# Main_PCB_Sig_only.net
KiCad netlist of a schematic drawn in EAGLE
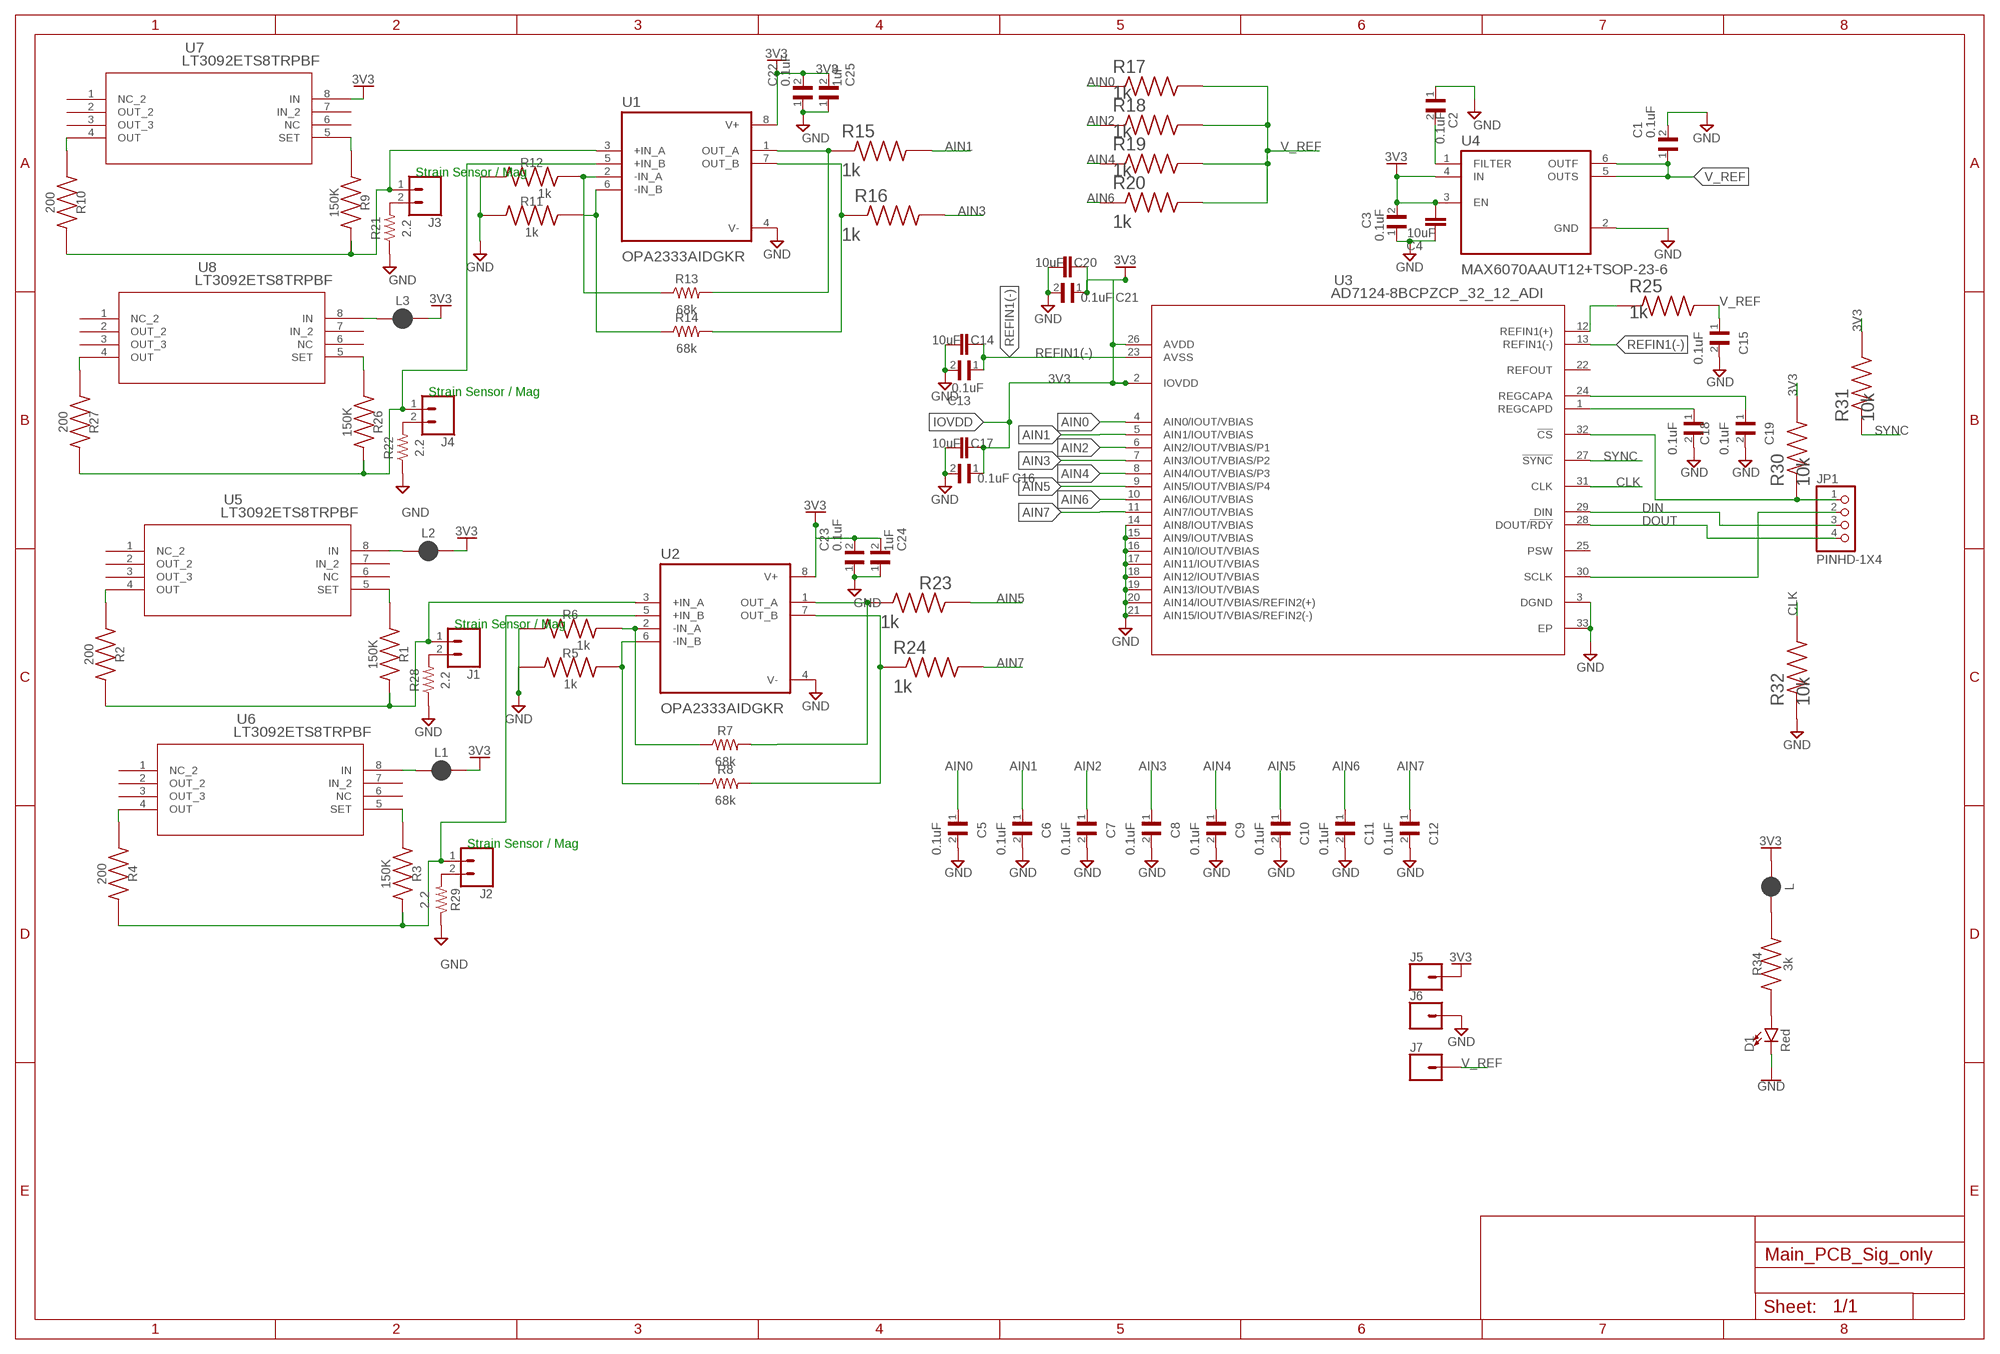
[diagram p0: schematic, sheet 1]

(export (version "E")
  (design (tool "Eeschema 10.0.6"))
  (components
    (comp (ref "C1")
      (value "0.1uF")
      (footprint "eagle-import:CAPC0603X33N")
      (fields (field (name "MF") "AVX") (field (name "MP") "0201ZD104KAT2A"))
      (libsource (lib "eagle-import") (part "0201ZD104KAT2A"))
    )
    (comp (ref "C2")
      (value "0.1uF")
      (footprint "eagle-import:CAPC0603X33N")
      (fields (field (name "MF") "AVX") (field (name "MP") "0201ZD104KAT2A"))
      (libsource (lib "eagle-import") (part "0201ZD104KAT2A"))
    )
    (comp (ref "C3")
      (value "0.1uF")
      (footprint "eagle-import:CAPC0603X33N")
      (fields (field (name "MF") "AVX") (field (name "MP") "0201ZD104KAT2A"))
      (libsource (lib "eagle-import") (part "0201ZD104KAT2A"))
    )
    (comp (ref "C4")
      (value "10uF")
      (footprint "eagle-import:CAPC1005X60")
      (libsource (lib "eagle-import") (part "CCHIP-0402(1005-METRIC)_"))
    )
    (comp (ref "C5")
      (value "0.1uF")
      (footprint "eagle-import:CAPC0603X33N")
      (fields (field (name "MF") "TDK") (field (name "MP") "C0603X7S1A104M030BC"))
      (libsource (lib "eagle-import") (part "C0603X7S1A104M030BC0201"))
    )
    (comp (ref "C6")
      (value "0.1uF")
      (footprint "eagle-import:CAPC0603X33N")
      (fields (field (name "MF") "TDK") (field (name "MP") "C0603X7S1A104M030BC"))
      (libsource (lib "eagle-import") (part "C0603X7S1A104M030BC0201"))
    )
    (comp (ref "C7")
      (value "0.1uF")
      (footprint "eagle-import:CAPC0603X33N")
      (fields (field (name "MF") "TDK") (field (name "MP") "C0603X7S1A104M030BC"))
      (libsource (lib "eagle-import") (part "C0603X7S1A104M030BC0201"))
    )
    (comp (ref "C8")
      (value "0.1uF")
      (footprint "eagle-import:CAPC0603X33N")
      (fields (field (name "MF") "TDK") (field (name "MP") "C0603X7S1A104M030BC"))
      (libsource (lib "eagle-import") (part "C0603X7S1A104M030BC0201"))
    )
    (comp (ref "C9")
      (value "0.1uF")
      (footprint "eagle-import:CAPC0603X33N")
      (fields (field (name "MF") "TDK") (field (name "MP") "C0603X7S1A104M030BC"))
      (libsource (lib "eagle-import") (part "C0603X7S1A104M030BC0201"))
    )
    (comp (ref "C10")
      (value "0.1uF")
      (footprint "eagle-import:CAPC0603X33N")
      (fields (field (name "MF") "TDK") (field (name "MP") "C0603X7S1A104M030BC"))
      (libsource (lib "eagle-import") (part "C0603X7S1A104M030BC0201"))
    )
    (comp (ref "C11")
      (value "0.1uF")
      (footprint "eagle-import:CAPC0603X33N")
      (fields (field (name "MF") "TDK") (field (name "MP") "C0603X7S1A104M030BC"))
      (libsource (lib "eagle-import") (part "C0603X7S1A104M030BC0201"))
    )
    (comp (ref "C12")
      (value "0.1uF")
      (footprint "eagle-import:CAPC0603X33N")
      (fields (field (name "MF") "TDK") (field (name "MP") "C0603X7S1A104M030BC"))
      (libsource (lib "eagle-import") (part "C0603X7S1A104M030BC0201"))
    )
    (comp (ref "C13")
      (value "0.1uF")
      (footprint "eagle-import:CAPC0603X33N")
      (fields (field (name "MF") "AVX") (field (name "MP") "0201ZD104KAT2A"))
      (libsource (lib "eagle-import") (part "0201ZD104KAT2A"))
    )
    (comp (ref "C14")
      (value "10uF")
      (footprint "eagle-import:CAPC1005X60")
      (libsource (lib "eagle-import") (part "CCHIP-0402(1005-METRIC)_"))
    )
    (comp (ref "C15")
      (value "0.1uF")
      (footprint "eagle-import:CAPC0603X33N")
      (fields (field (name "MF") "TDK") (field (name "MP") "C0603X7S1A104M030BC"))
      (libsource (lib "eagle-import") (part "C0603X7S1A104M030BC0201"))
    )
    (comp (ref "C16")
      (value "0.1uF")
      (footprint "eagle-import:CAPC0603X33N")
      (fields (field (name "MF") "AVX") (field (name "MP") "0201ZD104KAT2A"))
      (libsource (lib "eagle-import") (part "0201ZD104KAT2A"))
    )
    (comp (ref "C17")
      (value "10uF")
      (footprint "eagle-import:CAPC1005X60")
      (libsource (lib "eagle-import") (part "CCHIP-0402(1005-METRIC)_"))
    )
    (comp (ref "C18")
      (value "0.1uF")
      (footprint "eagle-import:CAPC0603X33N")
      (fields (field (name "MF") "TDK") (field (name "MP") "C0603X7S1A104M030BC"))
      (libsource (lib "eagle-import") (part "C0603X7S1A104M030BC0201"))
    )
    (comp (ref "C19")
      (value "0.1uF")
      (footprint "eagle-import:CAPC0603X33N")
      (fields (field (name "MF") "TDK") (field (name "MP") "C0603X7S1A104M030BC"))
      (libsource (lib "eagle-import") (part "C0603X7S1A104M030BC0201"))
    )
    (comp (ref "C20")
      (value "10uF")
      (footprint "eagle-import:CAPC1005X60")
      (libsource (lib "eagle-import") (part "CCHIP-0402(1005-METRIC)_"))
    )
    (comp (ref "C21")
      (value "0.1uF")
      (footprint "eagle-import:CAPC0603X33N")
      (fields (field (name "MF") "AVX") (field (name "MP") "0201ZD104KAT2A"))
      (libsource (lib "eagle-import") (part "0201ZD104KAT2A"))
    )
    (comp (ref "C22")
      (value "0.1uF")
      (footprint "eagle-import:CAPC0603X33N")
      (fields (field (name "MF") "AVX") (field (name "MP") "0201ZD104KAT2A"))
      (libsource (lib "eagle-import") (part "0201ZD104KAT2A"))
    )
    (comp (ref "C23")
      (value "0.1uF")
      (footprint "eagle-import:CAPC0603X33N")
      (fields (field (name "MF") "AVX") (field (name "MP") "0201ZD104KAT2A"))
      (libsource (lib "eagle-import") (part "0201ZD104KAT2A"))
    )
    (comp (ref "C24")
      (value "1uF")
      (footprint "eagle-import:CAPC0603X33N")
      (fields (field (name "MF") "AVX") (field (name "MP") "0201ZD104KAT2A"))
      (libsource (lib "eagle-import") (part "0201ZD104KAT2A"))
    )
    (comp (ref "C25")
      (value "1uF")
      (footprint "eagle-import:CAPC0603X33N")
      (fields (field (name "MF") "AVX") (field (name "MP") "0201ZD104KAT2A"))
      (libsource (lib "eagle-import") (part "0201ZD104KAT2A"))
    )
    (comp (ref "D1")
      (value "Red")
      (footprint "eagle-import:LED-0603")
      (libsource (lib "eagle-import") (part "LED-RED0603"))
    )
    (comp (ref "J1")
      (value "CONN_02")
      (footprint "eagle-import:1X02")
      (libsource (lib "eagle-import") (part "CONN_02"))
    )
    (comp (ref "J2")
      (value "CONN_02")
      (footprint "eagle-import:1X02")
      (libsource (lib "eagle-import") (part "CONN_02"))
    )
    (comp (ref "J3")
      (value "CONN_02")
      (footprint "eagle-import:1X02")
      (libsource (lib "eagle-import") (part "CONN_02"))
    )
    (comp (ref "J4")
      (value "CONN_02")
      (footprint "eagle-import:1X02")
      (libsource (lib "eagle-import") (part "CONN_02"))
    )
    (comp (ref "J5")
      (value "CONN_01PTH_LONGPAD")
      (footprint "eagle-import:1X01_LONGPAD")
      (libsource (lib "eagle-import") (part "CONN_01PTH_LONGPAD"))
    )
    (comp (ref "J6")
      (value "CONN_01PTH_LONGPAD")
      (footprint "eagle-import:1X01_LONGPAD")
      (libsource (lib "eagle-import") (part "CONN_01PTH_LONGPAD"))
    )
    (comp (ref "J7")
      (value "CONN_01PTH_LONGPAD")
      (footprint "eagle-import:1X01_LONGPAD")
      (libsource (lib "eagle-import") (part "CONN_01PTH_LONGPAD"))
    )
    (comp (ref "JP1")
      (value "PINHD-1X4")
      (footprint "eagle-import:1X04")
      (fields (field (name "MANUFACTURER") "Generic"))
      (libsource (lib "eagle-import") (part "PINHD-1X4"))
    )
    (comp (ref "L")
      (value "JUMPER-SMT_2_NC_PASTE_NO-SILK")
      (footprint "eagle-import:SMT-JUMPER_2_NC_PASTE_NO-SILK")
      (libsource (lib "eagle-import") (part "JUMPER-SMT_2_NC_PASTE_NO-SILK"))
    )
    (comp (ref "L1")
      (value "JUMPER-SMT_2_NC_PASTE_NO-SILK")
      (footprint "eagle-import:SMT-JUMPER_2_NC_PASTE_NO-SILK")
      (libsource (lib "eagle-import") (part "JUMPER-SMT_2_NC_PASTE_NO-SILK"))
    )
    (comp (ref "L2")
      (value "JUMPER-SMT_2_NC_PASTE_NO-SILK")
      (footprint "eagle-import:SMT-JUMPER_2_NC_PASTE_NO-SILK")
      (libsource (lib "eagle-import") (part "JUMPER-SMT_2_NC_PASTE_NO-SILK"))
    )
    (comp (ref "L3")
      (value "JUMPER-SMT_2_NC_PASTE_NO-SILK")
      (footprint "eagle-import:SMT-JUMPER_2_NC_PASTE_NO-SILK")
      (libsource (lib "eagle-import") (part "JUMPER-SMT_2_NC_PASTE_NO-SILK"))
    )
    (comp (ref "R1")
      (value "150K")
      (footprint "eagle-import:RESC0603X26N")
      (fields (field (name "MF") "Yageo") (field (name "MP") "AC0201FR-0710KL"))
      (libsource (lib "eagle-import") (part "AC0201FR-0710KL"))
    )
    (comp (ref "R2")
      (value "200")
      (footprint "eagle-import:RESC0603X26N")
      (fields (field (name "MF") "Yageo") (field (name "MP") "AC0201FR-0710KL"))
      (libsource (lib "eagle-import") (part "AC0201FR-0710KL"))
    )
    (comp (ref "R3")
      (value "150K")
      (footprint "eagle-import:RESC0603X26N")
      (fields (field (name "MF") "Yageo") (field (name "MP") "AC0201FR-0710KL"))
      (libsource (lib "eagle-import") (part "AC0201FR-0710KL"))
    )
    (comp (ref "R4")
      (value "200")
      (footprint "eagle-import:RESC0603X26N")
      (fields (field (name "MF") "Yageo") (field (name "MP") "AC0201FR-0710KL"))
      (libsource (lib "eagle-import") (part "AC0201FR-0710KL"))
    )
    (comp (ref "R5")
      (value "1k")
      (footprint "eagle-import:RESC0603X26N")
      (fields (field (name "MF") "Yageo") (field (name "MP") "AC0201FR-0710KL"))
      (libsource (lib "eagle-import") (part "AC0201FR-0710KL"))
    )
    (comp (ref "R6")
      (value "1k")
      (footprint "eagle-import:RESC0603X26N")
      (fields (field (name "MF") "Yageo") (field (name "MP") "AC0201FR-0710KL"))
      (libsource (lib "eagle-import") (part "AC0201FR-0710KL"))
    )
    (comp (ref "R7")
      (value "68k")
      (footprint "eagle-import:RESC1608X60")
      (libsource (lib "eagle-import") (part "R-USCHIP-0603(1608-METRIC)_"))
    )
    (comp (ref "R8")
      (value "68k")
      (footprint "eagle-import:RESC1608X60")
      (libsource (lib "eagle-import") (part "R-USCHIP-0603(1608-METRIC)_"))
    )
    (comp (ref "R9")
      (value "150K")
      (footprint "eagle-import:RESC0603X26N")
      (fields (field (name "MF") "Yageo") (field (name "MP") "AC0201FR-0710KL"))
      (libsource (lib "eagle-import") (part "AC0201FR-0710KL"))
    )
    (comp (ref "R10")
      (value "200")
      (footprint "eagle-import:RESC0603X26N")
      (fields (field (name "MF") "Yageo") (field (name "MP") "AC0201FR-0710KL"))
      (libsource (lib "eagle-import") (part "AC0201FR-0710KL"))
    )
    (comp (ref "R11")
      (value "1k")
      (footprint "eagle-import:RESC0603X26N")
      (fields (field (name "MF") "Yageo") (field (name "MP") "AC0201FR-0710KL"))
      (libsource (lib "eagle-import") (part "AC0201FR-0710KL"))
    )
    (comp (ref "R12")
      (value "1k")
      (footprint "eagle-import:RESC0603X26N")
      (fields (field (name "MF") "Yageo") (field (name "MP") "AC0201FR-0710KL"))
      (libsource (lib "eagle-import") (part "AC0201FR-0710KL"))
    )
    (comp (ref "R13")
      (value "68k")
      (footprint "eagle-import:RESC1608X60")
      (libsource (lib "eagle-import") (part "R-USCHIP-0603(1608-METRIC)_"))
    )
    (comp (ref "R14")
      (value "68k")
      (footprint "eagle-import:RESC1608X60")
      (libsource (lib "eagle-import") (part "R-USCHIP-0603(1608-METRIC)_"))
    )
    (comp (ref "R15")
      (value "1k")
      (footprint "eagle-import:RESC0603X26N")
      (fields (field (name "MF") "Yageo") (field (name "MP") "AC0201FR-0710KL"))
      (libsource (lib "eagle-import") (part "AC0201FR-0710KL"))
    )
    (comp (ref "R16")
      (value "1k")
      (footprint "eagle-import:RESC0603X26N")
      (fields (field (name "MF") "Yageo") (field (name "MP") "AC0201FR-0710KL"))
      (libsource (lib "eagle-import") (part "AC0201FR-0710KL"))
    )
    (comp (ref "R17")
      (value "1k")
      (footprint "eagle-import:RESC0603X26N")
      (fields (field (name "MF") "Yageo") (field (name "MP") "AC0201FR-0710KL"))
      (libsource (lib "eagle-import") (part "AC0201FR-0710KL"))
    )
    (comp (ref "R18")
      (value "1k")
      (footprint "eagle-import:RESC0603X26N")
      (fields (field (name "MF") "Yageo") (field (name "MP") "AC0201FR-0710KL"))
      (libsource (lib "eagle-import") (part "AC0201FR-0710KL"))
    )
    (comp (ref "R19")
      (value "1k")
      (footprint "eagle-import:RESC0603X26N")
      (fields (field (name "MF") "Yageo") (field (name "MP") "AC0201FR-0710KL"))
      (libsource (lib "eagle-import") (part "AC0201FR-0710KL"))
    )
    (comp (ref "R20")
      (value "1k")
      (footprint "eagle-import:RESC0603X26N")
      (fields (field (name "MF") "Yageo") (field (name "MP") "AC0201FR-0710KL"))
      (libsource (lib "eagle-import") (part "AC0201FR-0710KL"))
    )
    (comp (ref "R21")
      (value "2.2")
      (footprint "eagle-import:RESC1608X60")
      (libsource (lib "eagle-import") (part "R-USCHIP-0603(1608-METRIC)_"))
    )
    (comp (ref "R22")
      (value "2.2")
      (footprint "eagle-import:RESC1608X60")
      (libsource (lib "eagle-import") (part "R-USCHIP-0603(1608-METRIC)_"))
    )
    (comp (ref "R23")
      (value "1k")
      (footprint "eagle-import:RESC0603X26N")
      (fields (field (name "MF") "Yageo") (field (name "MP") "AC0201FR-0710KL"))
      (libsource (lib "eagle-import") (part "AC0201FR-0710KL"))
    )
    (comp (ref "R24")
      (value "1k")
      (footprint "eagle-import:RESC0603X26N")
      (fields (field (name "MF") "Yageo") (field (name "MP") "AC0201FR-0710KL"))
      (libsource (lib "eagle-import") (part "AC0201FR-0710KL"))
    )
    (comp (ref "R25")
      (value "1k")
      (footprint "eagle-import:RESC0603X26N")
      (fields (field (name "MF") "Yageo") (field (name "MP") "AC0201FR-0710KL"))
      (libsource (lib "eagle-import") (part "AC0201FR-0710KL"))
    )
    (comp (ref "R26")
      (value "150K")
      (footprint "eagle-import:RESC0603X26N")
      (fields (field (name "MF") "Yageo") (field (name "MP") "AC0201FR-0710KL"))
      (libsource (lib "eagle-import") (part "AC0201FR-0710KL"))
    )
    (comp (ref "R27")
      (value "200")
      (footprint "eagle-import:RESC0603X26N")
      (fields (field (name "MF") "Yageo") (field (name "MP") "AC0201FR-0710KL"))
      (libsource (lib "eagle-import") (part "AC0201FR-0710KL"))
    )
    (comp (ref "R28")
      (value "2.2")
      (footprint "eagle-import:RESC1608X60")
      (libsource (lib "eagle-import") (part "R-USCHIP-0603(1608-METRIC)_"))
    )
    (comp (ref "R29")
      (value "2.2")
      (footprint "eagle-import:RESC1608X60")
      (libsource (lib "eagle-import") (part "R-USCHIP-0603(1608-METRIC)_"))
    )
    (comp (ref "R30")
      (value "10k")
      (footprint "eagle-import:RESC0603X26N")
      (fields (field (name "MF") "Yageo") (field (name "MP") "AC0201FR-0710KL"))
      (libsource (lib "eagle-import") (part "AC0201FR-0710KL"))
    )
    (comp (ref "R31")
      (value "10k")
      (footprint "eagle-import:RESC0603X26N")
      (fields (field (name "MF") "Yageo") (field (name "MP") "AC0201FR-0710KL"))
      (libsource (lib "eagle-import") (part "AC0201FR-0710KL"))
    )
    (comp (ref "R32")
      (value "10k")
      (footprint "eagle-import:RESC0603X26N")
      (fields (field (name "MF") "Yageo") (field (name "MP") "AC0201FR-0710KL"))
      (libsource (lib "eagle-import") (part "AC0201FR-0710KL"))
    )
    (comp (ref "R34")
      (value "3k")
      (footprint "eagle-import:RESC0603X26N")
      (fields (field (name "MF") "Yageo") (field (name "MP") "AC0201FR-0710KL"))
      (libsource (lib "eagle-import") (part "AC0201FR-0710KL"))
    )
    (comp (ref "U1")
      (value "OPA2333AIDGKR")
      (footprint "eagle-import:SOP65P490X110-8N")
      (fields (field (name "MF") "Texas Instruments"))
      (libsource (lib "eagle-import") (part "OPA2333AIDGKR"))
    )
    (comp (ref "U2")
      (value "OPA2333AIDGKR")
      (footprint "eagle-import:SOP65P490X110-8N")
      (fields (field (name "MF") "Texas Instruments"))
      (libsource (lib "eagle-import") (part "OPA2333AIDGKR"))
    )
    (comp (ref "U3")
      (value "AD7124-8BCPZCP_32_12_ADI")
      (footprint "eagle-import:CP_32_12_ADI")
      (fields
        (field (name "MANUFACTURER_PART_NUMBER") "AD7124-8BCPZ")
        (field (name "COPYRIGHT") "Copyright (C) 2025 Ultra Librarian. All rights reserved.")
      )
      (libsource (lib "eagle-import") (part "AD7124-8BCPZCP_32_12_ADI"))
    )
    (comp (ref "U4")
      (value "MAX6070AAUT12+TSOP-23-6")
      (footprint "eagle-import:SOT95P280X145-6N")
      (fields (field (name "MF") "Maxim Integrated Products") (field (name "MP") "MAX6070AAUT12+T"))
      (libsource (lib "eagle-import") (part "MAX6070AAUT12+TSOP-23-6"))
    )
    (comp (ref "U5")
      (value "LT3092ETS8TRPBF")
      (footprint "eagle-import:TSOT-23_TS8")
      (fields (field (name "MF") "Analog Devices") (field (name "MP") "LT3092ETS8#TRPBF"))
      (libsource (lib "eagle-import") (part "LT3092ETS8TRPBF"))
    )
    (comp (ref "U6")
      (value "LT3092ETS8TRPBF")
      (footprint "eagle-import:TSOT-23_TS8")
      (fields (field (name "MF") "Analog Devices") (field (name "MP") "LT3092ETS8#TRPBF"))
      (libsource (lib "eagle-import") (part "LT3092ETS8TRPBF"))
    )
    (comp (ref "U7")
      (value "LT3092ETS8TRPBF")
      (footprint "eagle-import:TSOT-23_TS8")
      (fields (field (name "MF") "Analog Devices") (field (name "MP") "LT3092ETS8#TRPBF"))
      (libsource (lib "eagle-import") (part "LT3092ETS8TRPBF"))
    )
    (comp (ref "U8")
      (value "LT3092ETS8TRPBF")
      (footprint "eagle-import:TSOT-23_TS8")
      (fields (field (name "MF") "Analog Devices") (field (name "MP") "LT3092ETS8#TRPBF"))
      (libsource (lib "eagle-import") (part "LT3092ETS8TRPBF"))
    )
  )
  (nets
    (net (code "1") (name "/CLK") (class "Default")
      (node (ref "R32") (pin "2") (pinfunction "2_2") (pintype "passive"))
      (node (ref "U3") (pin "31") (pinfunction "CLK_31") (pintype "passive"))
    )
    (net (code "2") (name "/DIN") (class "Default")
      (node (ref "JP1") (pin "3") (pinfunction "3_3") (pintype "passive"))
      (node (ref "U3") (pin "29") (pinfunction "DIN_29") (pintype "passive"))
    )
    (net (code "3") (name "/DOUT") (class "Default")
      (node (ref "JP1") (pin "4") (pinfunction "4_4") (pintype "passive"))
      (node (ref "U3") (pin "28") (pinfunction "DOUT/~{RDY}_28") (pintype "passive"))
    )
    (net (code "4") (name "/SYNC") (class "Default")
      (node (ref "R31") (pin "1") (pinfunction "1_1") (pintype "passive"))
      (node (ref "U3") (pin "27") (pinfunction "~{SYNC}_27") (pintype "passive"))
    )
    (net (code "5") (name "AIN0") (class "Default")
      (node (ref "C5") (pin "1") (pinfunction "1_1") (pintype "passive"))
      (node (ref "R17") (pin "1") (pinfunction "1_1") (pintype "passive"))
      (node (ref "U3") (pin "4") (pinfunction "AIN0/IOUT/VBIAS_4") (pintype "passive"))
    )
    (net (code "6") (name "AIN1") (class "Default")
      (node (ref "C6") (pin "1") (pinfunction "1_1") (pintype "passive"))
      (node (ref "R15") (pin "2") (pinfunction "2_2") (pintype "passive"))
      (node (ref "U3") (pin "5") (pinfunction "AIN1/IOUT/VBIAS_5") (pintype "passive"))
    )
    (net (code "7") (name "AIN2") (class "Default")
      (node (ref "C7") (pin "1") (pinfunction "1_1") (pintype "passive"))
      (node (ref "R18") (pin "1") (pinfunction "1_1") (pintype "passive"))
      (node (ref "U3") (pin "6") (pinfunction "AIN2/IOUT/VBIAS/P1_6") (pintype "passive"))
    )
    (net (code "8") (name "AIN3") (class "Default")
      (node (ref "C8") (pin "1") (pinfunction "1_1") (pintype "passive"))
      (node (ref "R16") (pin "2") (pinfunction "2_2") (pintype "passive"))
      (node (ref "U3") (pin "7") (pinfunction "AIN3/IOUT/VBIAS/P2_7") (pintype "passive"))
    )
    (net (code "9") (name "AIN4") (class "Default")
      (node (ref "C9") (pin "1") (pinfunction "1_1") (pintype "passive"))
      (node (ref "R19") (pin "1") (pinfunction "1_1") (pintype "passive"))
      (node (ref "U3") (pin "8") (pinfunction "AIN4/IOUT/VBIAS/P3_8") (pintype "passive"))
    )
    (net (code "10") (name "AIN5") (class "Default")
      (node (ref "C10") (pin "1") (pinfunction "1_1") (pintype "passive"))
      (node (ref "R23") (pin "2") (pinfunction "2_2") (pintype "passive"))
      (node (ref "U3") (pin "9") (pinfunction "AIN5/IOUT/VBIAS/P4_9") (pintype "passive"))
    )
    (net (code "11") (name "AIN6") (class "Default")
      (node (ref "C11") (pin "1") (pinfunction "1_1") (pintype "passive"))
      (node (ref "R20") (pin "1") (pinfunction "1_1") (pintype "passive"))
      (node (ref "U3") (pin "10") (pinfunction "AIN6/IOUT/VBIAS_10") (pintype "passive"))
    )
    (net (code "12") (name "AIN7") (class "Default")
      (node (ref "C12") (pin "1") (pinfunction "1_1") (pintype "passive"))
      (node (ref "R24") (pin "2") (pinfunction "2_2") (pintype "passive"))
      (node (ref "U3") (pin "11") (pinfunction "AIN7/IOUT/VBIAS_11") (pintype "passive"))
    )
    (net (code "13") (name "GND") (class "Default")
      (node (ref "C1") (pin "2") (pinfunction "2_2") (pintype "passive"))
      (node (ref "C10") (pin "2") (pinfunction "2_2") (pintype "passive"))
      (node (ref "C11") (pin "2") (pinfunction "2_2") (pintype "passive"))
      (node (ref "C12") (pin "2") (pinfunction "2_2") (pintype "passive"))
      (node (ref "C13") (pin "2") (pinfunction "2_2") (pintype "passive"))
      (node (ref "C14") (pin "2") (pinfunction "2_2") (pintype "passive"))
      (node (ref "C15") (pin "2") (pinfunction "2_2") (pintype "passive"))
      (node (ref "C16") (pin "2") (pinfunction "2_2") (pintype "passive"))
      (node (ref "C17") (pin "2") (pinfunction "2_2") (pintype "passive"))
      (node (ref "C18") (pin "2") (pinfunction "2_2") (pintype "passive"))
      (node (ref "C19") (pin "2") (pinfunction "2_2") (pintype "passive"))
      (node (ref "C2") (pin "1") (pinfunction "1_1") (pintype "passive"))
      (node (ref "C20") (pin "2") (pinfunction "2_2") (pintype "passive"))
      (node (ref "C21") (pin "2") (pinfunction "2_2") (pintype "passive"))
      (node (ref "C22") (pin "1") (pinfunction "1_1") (pintype "passive"))
      (node (ref "C23") (pin "1") (pinfunction "1_1") (pintype "passive"))
      (node (ref "C24") (pin "1") (pinfunction "1_1") (pintype "passive"))
      (node (ref "C25") (pin "1") (pinfunction "1_1") (pintype "passive"))
      (node (ref "C3") (pin "1") (pinfunction "1_1") (pintype "passive"))
      (node (ref "C4") (pin "1") (pinfunction "1_1") (pintype "passive"))
      (node (ref "C5") (pin "2") (pinfunction "2_2") (pintype "passive"))
      (node (ref "C6") (pin "2") (pinfunction "2_2") (pintype "passive"))
      (node (ref "C7") (pin "2") (pinfunction "2_2") (pintype "passive"))
      (node (ref "C8") (pin "2") (pinfunction "2_2") (pintype "passive"))
      (node (ref "C9") (pin "2") (pinfunction "2_2") (pintype "passive"))
      (node (ref "D1") (pin "C") (pinfunction "C_C") (pintype "passive"))
      (node (ref "J6") (pin "1") (pinfunction "1_1") (pintype "passive"))
      (node (ref "R11") (pin "1") (pinfunction "1_1") (pintype "passive"))
      (node (ref "R12") (pin "1") (pinfunction "1_1") (pintype "passive"))
      (node (ref "R21") (pin "1") (pinfunction "1_1") (pintype "passive"))
      (node (ref "R22") (pin "1") (pinfunction "1_1") (pintype "passive"))
      (node (ref "R28") (pin "1") (pinfunction "1_1") (pintype "passive"))
      (node (ref "R29") (pin "1") (pinfunction "1_1") (pintype "passive"))
      (node (ref "R32") (pin "1") (pinfunction "1_1") (pintype "passive"))
      (node (ref "R5") (pin "1") (pinfunction "1_1") (pintype "passive"))
      (node (ref "R6") (pin "1") (pinfunction "1_1") (pintype "passive"))
      (node (ref "U1") (pin "4") (pinfunction "V-_4") (pintype "power_in"))
      (node (ref "U2") (pin "4") (pinfunction "V-_4") (pintype "power_in"))
      (node (ref "U3") (pin "14") (pinfunction "AIN8/IOUT/VBIAS_14") (pintype "passive"))
      (node (ref "U3") (pin "15") (pinfunction "AIN9/IOUT/VBIAS_15") (pintype "passive"))
      (node (ref "U3") (pin "16") (pinfunction "AIN10/IOUT/VBIAS_16") (pintype "passive"))
      (node (ref "U3") (pin "17") (pinfunction "AIN11/IOUT/VBIAS_17") (pintype "passive"))
      (node (ref "U3") (pin "18") (pinfunction "AIN12/IOUT/VBIAS_18") (pintype "passive"))
      (node (ref "U3") (pin "19") (pinfunction "AIN13/IOUT/VBIAS_19") (pintype "passive"))
      (node (ref "U3") (pin "20") (pinfunction "AIN14/IOUT/VBIAS/REFIN2(+)_20") (pintype "passive"))
      (node (ref "U3") (pin "21") (pinfunction "AIN15/IOUT/VBIAS/REFIN2(-)_21") (pintype "passive"))
      (node (ref "U3") (pin "3") (pinfunction "DGND_3") (pintype "passive"))
      (node (ref "U3") (pin "33") (pinfunction "EP_33") (pintype "passive"))
      (node (ref "U4") (pin "2") (pinfunction "GND_2") (pintype "power_in"))
    )
    (net (code "14") (name "IOVDD") (class "Default")
      (node (ref "C16") (pin "1") (pinfunction "1_1") (pintype "passive"))
      (node (ref "C17") (pin "1") (pinfunction "1_1") (pintype "passive"))
      (node (ref "C20") (pin "1") (pinfunction "1_1") (pintype "passive"))
      (node (ref "C21") (pin "1") (pinfunction "1_1") (pintype "passive"))
      (node (ref "C22") (pin "2") (pinfunction "2_2") (pintype "passive"))
      (node (ref "C23") (pin "2") (pinfunction "2_2") (pintype "passive"))
      (node (ref "C24") (pin "2") (pinfunction "2_2") (pintype "passive"))
      (node (ref "C25") (pin "2") (pinfunction "2_2") (pintype "passive"))
      (node (ref "C3") (pin "2") (pinfunction "2_2") (pintype "passive"))
      (node (ref "C4") (pin "2") (pinfunction "2_2") (pintype "passive"))
      (node (ref "J5") (pin "1") (pinfunction "1_1") (pintype "passive"))
      (node (ref "L") (pin "1") (pinfunction "1_1") (pintype "passive"))
      (node (ref "L1") (pin "2") (pinfunction "2_2") (pintype "passive"))
      (node (ref "L2") (pin "2") (pinfunction "2_2") (pintype "passive"))
      (node (ref "L3") (pin "2") (pinfunction "2_2") (pintype "passive"))
      (node (ref "R30") (pin "2") (pinfunction "2_2") (pintype "passive"))
      (node (ref "R31") (pin "2") (pinfunction "2_2") (pintype "passive"))
      (node (ref "U1") (pin "8") (pinfunction "V+_8") (pintype "power_in"))
      (node (ref "U2") (pin "8") (pinfunction "V+_8") (pintype "power_in"))
      (node (ref "U3") (pin "2") (pinfunction "IOVDD_2") (pintype "passive"))
      (node (ref "U3") (pin "26") (pinfunction "AVDD_26") (pintype "passive"))
      (node (ref "U4") (pin "3") (pinfunction "EN_3") (pintype "bidirectional"))
      (node (ref "U4") (pin "4") (pinfunction "IN_4") (pintype "input"))
      (node (ref "U7") (pin "8") (pinfunction "IN_8") (pintype "input"))
    )
    (net (code "15") (name "Net-(D1-PadA)") (class "Default")
      (node (ref "D1") (pin "A") (pinfunction "A_A") (pintype "passive"))
      (node (ref "R34") (pin "1") (pinfunction "1_1") (pintype "passive"))
    )
    (net (code "16") (name "Net-(J1-Pad2)") (class "Default")
      (node (ref "J1") (pin "2") (pinfunction "2_2") (pintype "passive"))
      (node (ref "R28") (pin "2") (pinfunction "2_2") (pintype "passive"))
    )
    (net (code "17") (name "Net-(J2-Pad2)") (class "Default")
      (node (ref "J2") (pin "2") (pinfunction "2_2") (pintype "passive"))
      (node (ref "R29") (pin "2") (pinfunction "2_2") (pintype "passive"))
    )
    (net (code "18") (name "Net-(J3-Pad2)") (class "Default")
      (node (ref "J3") (pin "2") (pinfunction "2_2") (pintype "passive"))
      (node (ref "R21") (pin "2") (pinfunction "2_2") (pintype "passive"))
    )
    (net (code "19") (name "Net-(J4-Pad2)") (class "Default")
      (node (ref "J4") (pin "2") (pinfunction "2_2") (pintype "passive"))
      (node (ref "R22") (pin "2") (pinfunction "2_2") (pintype "passive"))
    )
    (net (code "20") (name "Net-(L-Pad2)") (class "Default")
      (node (ref "L") (pin "2") (pinfunction "2_2") (pintype "passive"))
      (node (ref "R34") (pin "2") (pinfunction "2_2") (pintype "passive"))
    )
    (net (code "21") (name "Net-(U1-+IN_A)") (class "Default")
      (node (ref "J3") (pin "1") (pinfunction "1_1") (pintype "passive"))
      (node (ref "R10") (pin "2") (pinfunction "2_2") (pintype "passive"))
      (node (ref "R9") (pin "2") (pinfunction "2_2") (pintype "passive"))
      (node (ref "U1") (pin "3") (pinfunction "+IN_A_3") (pintype "input"))
    )
    (net (code "22") (name "Net-(U1-+IN_B)") (class "Default")
      (node (ref "J4") (pin "1") (pinfunction "1_1") (pintype "passive"))
      (node (ref "R26") (pin "2") (pinfunction "2_2") (pintype "passive"))
      (node (ref "R27") (pin "2") (pinfunction "2_2") (pintype "passive"))
      (node (ref "U1") (pin "5") (pinfunction "+IN_B_5") (pintype "input"))
    )
    (net (code "23") (name "Net-(U1--IN_A)") (class "Default")
      (node (ref "R12") (pin "2") (pinfunction "2_2") (pintype "passive"))
      (node (ref "R13") (pin "1") (pinfunction "1_1") (pintype "passive"))
      (node (ref "U1") (pin "2") (pinfunction "-IN_A_2") (pintype "input"))
    )
    (net (code "24") (name "Net-(U1--IN_B)") (class "Default")
      (node (ref "R11") (pin "2") (pinfunction "2_2") (pintype "passive"))
      (node (ref "R14") (pin "1") (pinfunction "1_1") (pintype "passive"))
      (node (ref "U1") (pin "6") (pinfunction "-IN_B_6") (pintype "input"))
    )
    (net (code "25") (name "Net-(U1-OUT_A)") (class "Default")
      (node (ref "R13") (pin "2") (pinfunction "2_2") (pintype "passive"))
      (node (ref "R15") (pin "1") (pinfunction "1_1") (pintype "passive"))
      (node (ref "U1") (pin "1") (pinfunction "OUT_A_1") (pintype "output"))
    )
    (net (code "26") (name "Net-(U1-OUT_B)") (class "Default")
      (node (ref "R14") (pin "2") (pinfunction "2_2") (pintype "passive"))
      (node (ref "R16") (pin "1") (pinfunction "1_1") (pintype "passive"))
      (node (ref "U1") (pin "7") (pinfunction "OUT_B_7") (pintype "output"))
    )
    (net (code "27") (name "Net-(U2-+IN_A)") (class "Default")
      (node (ref "J1") (pin "1") (pinfunction "1_1") (pintype "passive"))
      (node (ref "R1") (pin "2") (pinfunction "2_2") (pintype "passive"))
      (node (ref "R2") (pin "2") (pinfunction "2_2") (pintype "passive"))
      (node (ref "U2") (pin "3") (pinfunction "+IN_A_3") (pintype "input"))
    )
    (net (code "28") (name "Net-(U2-+IN_B)") (class "Default")
      (node (ref "J2") (pin "1") (pinfunction "1_1") (pintype "passive"))
      (node (ref "R3") (pin "2") (pinfunction "2_2") (pintype "passive"))
      (node (ref "R4") (pin "2") (pinfunction "2_2") (pintype "passive"))
      (node (ref "U2") (pin "5") (pinfunction "+IN_B_5") (pintype "input"))
    )
    (net (code "29") (name "Net-(U2--IN_A)") (class "Default")
      (node (ref "R6") (pin "2") (pinfunction "2_2") (pintype "passive"))
      (node (ref "R7") (pin "1") (pinfunction "1_1") (pintype "passive"))
      (node (ref "U2") (pin "2") (pinfunction "-IN_A_2") (pintype "input"))
    )
    (net (code "30") (name "Net-(U2--IN_B)") (class "Default")
      (node (ref "R5") (pin "2") (pinfunction "2_2") (pintype "passive"))
      (node (ref "R8") (pin "1") (pinfunction "1_1") (pintype "passive"))
      (node (ref "U2") (pin "6") (pinfunction "-IN_B_6") (pintype "input"))
    )
    (net (code "31") (name "Net-(U2-OUT_A)") (class "Default")
      (node (ref "R23") (pin "1") (pinfunction "1_1") (pintype "passive"))
      (node (ref "R7") (pin "2") (pinfunction "2_2") (pintype "passive"))
      (node (ref "U2") (pin "1") (pinfunction "OUT_A_1") (pintype "output"))
    )
    (net (code "32") (name "Net-(U2-OUT_B)") (class "Default")
      (node (ref "R24") (pin "1") (pinfunction "1_1") (pintype "passive"))
      (node (ref "R8") (pin "2") (pinfunction "2_2") (pintype "passive"))
      (node (ref "U2") (pin "7") (pinfunction "OUT_B_7") (pintype "output"))
    )
    (net (code "33") (name "Net-(U3-REFIN1(+))") (class "Default")
      (node (ref "R25") (pin "1") (pinfunction "1_1") (pintype "passive"))
      (node (ref "U3") (pin "12") (pinfunction "REFIN1(+)_12") (pintype "passive"))
    )
    (net (code "34") (name "Net-(U3-REGCAPA)") (class "Default")
      (node (ref "C19") (pin "1") (pinfunction "1_1") (pintype "passive"))
      (node (ref "U3") (pin "24") (pinfunction "REGCAPA_24") (pintype "passive"))
    )
    (net (code "35") (name "Net-(U3-REGCAPD)") (class "Default")
      (node (ref "C18") (pin "1") (pinfunction "1_1") (pintype "passive"))
      (node (ref "U3") (pin "1") (pinfunction "REGCAPD_1") (pintype "passive"))
    )
    (net (code "36") (name "Net-(U3-SCLK)") (class "Default")
      (node (ref "JP1") (pin "2") (pinfunction "2_2") (pintype "passive"))
      (node (ref "U3") (pin "30") (pinfunction "SCLK_30") (pintype "passive"))
    )
    (net (code "37") (name "Net-(U3-~{CS})") (class "Default")
      (node (ref "JP1") (pin "1") (pinfunction "1_1") (pintype "passive"))
      (node (ref "R30") (pin "1") (pinfunction "1_1") (pintype "passive"))
      (node (ref "U3") (pin "32") (pinfunction "~{CS}_32") (pintype "passive"))
    )
    (net (code "38") (name "Net-(U4-FILTER)") (class "Default")
      (node (ref "C2") (pin "2") (pinfunction "2_2") (pintype "passive"))
      (node (ref "U4") (pin "1") (pinfunction "FILTER_1") (pintype "input"))
    )
    (net (code "39") (name "Net-(U5-IN)") (class "Default")
      (node (ref "L2") (pin "1") (pinfunction "1_1") (pintype "passive"))
      (node (ref "U5") (pin "8") (pinfunction "IN_8") (pintype "input"))
    )
    (net (code "40") (name "Net-(U5-OUT)") (class "Default")
      (node (ref "R2") (pin "1") (pinfunction "1_1") (pintype "passive"))
      (node (ref "U5") (pin "4") (pinfunction "OUT_4") (pintype "output"))
    )
    (net (code "41") (name "Net-(U5-SET)") (class "Default")
      (node (ref "R1") (pin "1") (pinfunction "1_1") (pintype "passive"))
      (node (ref "U5") (pin "5") (pinfunction "SET_5") (pintype "input"))
    )
    (net (code "42") (name "Net-(U6-IN)") (class "Default")
      (node (ref "L1") (pin "1") (pinfunction "1_1") (pintype "passive"))
      (node (ref "U6") (pin "8") (pinfunction "IN_8") (pintype "input"))
    )
    (net (code "43") (name "Net-(U6-OUT)") (class "Default")
      (node (ref "R4") (pin "1") (pinfunction "1_1") (pintype "passive"))
      (node (ref "U6") (pin "4") (pinfunction "OUT_4") (pintype "output"))
    )
    (net (code "44") (name "Net-(U6-SET)") (class "Default")
      (node (ref "R3") (pin "1") (pinfunction "1_1") (pintype "passive"))
      (node (ref "U6") (pin "5") (pinfunction "SET_5") (pintype "input"))
    )
    (net (code "45") (name "Net-(U7-OUT)") (class "Default")
      (node (ref "R10") (pin "1") (pinfunction "1_1") (pintype "passive"))
      (node (ref "U7") (pin "4") (pinfunction "OUT_4") (pintype "output"))
    )
    (net (code "46") (name "Net-(U7-SET)") (class "Default")
      (node (ref "R9") (pin "1") (pinfunction "1_1") (pintype "passive"))
      (node (ref "U7") (pin "5") (pinfunction "SET_5") (pintype "input"))
    )
    (net (code "47") (name "Net-(U8-IN)") (class "Default")
      (node (ref "L3") (pin "1") (pinfunction "1_1") (pintype "passive"))
      (node (ref "U8") (pin "8") (pinfunction "IN_8") (pintype "input"))
    )
    (net (code "48") (name "Net-(U8-OUT)") (class "Default")
      (node (ref "R27") (pin "1") (pinfunction "1_1") (pintype "passive"))
      (node (ref "U8") (pin "4") (pinfunction "OUT_4") (pintype "output"))
    )
    (net (code "49") (name "Net-(U8-SET)") (class "Default")
      (node (ref "R26") (pin "1") (pinfunction "1_1") (pintype "passive"))
      (node (ref "U8") (pin "5") (pinfunction "SET_5") (pintype "input"))
    )
    (net (code "50") (name "REFIN1(-)") (class "Default")
      (node (ref "C13") (pin "1") (pinfunction "1_1") (pintype "passive"))
      (node (ref "C14") (pin "1") (pinfunction "1_1") (pintype "passive"))
      (node (ref "U3") (pin "13") (pinfunction "REFIN1(-)_13") (pintype "passive"))
      (node (ref "U3") (pin "23") (pinfunction "AVSS_23") (pintype "passive"))
    )
    (net (code "51") (name "V_REF") (class "Default")
      (node (ref "C1") (pin "1") (pinfunction "1_1") (pintype "passive"))
      (node (ref "C15") (pin "1") (pinfunction "1_1") (pintype "passive"))
      (node (ref "J7") (pin "1") (pinfunction "1_1") (pintype "passive"))
      (node (ref "R17") (pin "2") (pinfunction "2_2") (pintype "passive"))
      (node (ref "R18") (pin "2") (pinfunction "2_2") (pintype "passive"))
      (node (ref "R19") (pin "2") (pinfunction "2_2") (pintype "passive"))
      (node (ref "R20") (pin "2") (pinfunction "2_2") (pintype "passive"))
      (node (ref "R25") (pin "2") (pinfunction "2_2") (pintype "passive"))
      (node (ref "U4") (pin "5") (pinfunction "OUTS_5") (pintype "output"))
      (node (ref "U4") (pin "6") (pinfunction "OUTF_6") (pintype "output"))
    )
    (net (code "52") (name "unconnected-(U3-PSW-Pad25)") (class "Default")
      (node (ref "U3") (pin "25") (pinfunction "PSW_25") (pintype "passive"))
    )
    (net (code "53") (name "unconnected-(U3-REFOUT-Pad22)") (class "Default")
      (node (ref "U3") (pin "22") (pinfunction "REFOUT_22") (pintype "passive"))
    )
    (net (code "54") (name "unconnected-(U5-IN_2-Pad7)") (class "Default")
      (node (ref "U5") (pin "7") (pinfunction "IN_2_7") (pintype "input"))
    )
    (net (code "55") (name "unconnected-(U5-NC-Pad6)") (class "Default")
      (node (ref "U5") (pin "6") (pinfunction "NC_6") (pintype "no_connect"))
    )
    (net (code "56") (name "unconnected-(U5-NC_2-Pad1)") (class "Default")
      (node (ref "U5") (pin "1") (pinfunction "NC_2_1") (pintype "no_connect"))
    )
    (net (code "57") (name "unconnected-(U5-OUT_2-Pad2)") (class "Default")
      (node (ref "U5") (pin "2") (pinfunction "OUT_2_2") (pintype "output"))
    )
    (net (code "58") (name "unconnected-(U5-OUT_3-Pad3)") (class "Default")
      (node (ref "U5") (pin "3") (pinfunction "OUT_3_3") (pintype "output"))
    )
    (net (code "59") (name "unconnected-(U6-IN_2-Pad7)") (class "Default")
      (node (ref "U6") (pin "7") (pinfunction "IN_2_7") (pintype "input"))
    )
    (net (code "60") (name "unconnected-(U6-NC-Pad6)") (class "Default")
      (node (ref "U6") (pin "6") (pinfunction "NC_6") (pintype "no_connect"))
    )
    (net (code "61") (name "unconnected-(U6-NC_2-Pad1)") (class "Default")
      (node (ref "U6") (pin "1") (pinfunction "NC_2_1") (pintype "no_connect"))
    )
    (net (code "62") (name "unconnected-(U6-OUT_2-Pad2)") (class "Default")
      (node (ref "U6") (pin "2") (pinfunction "OUT_2_2") (pintype "output"))
    )
    (net (code "63") (name "unconnected-(U6-OUT_3-Pad3)") (class "Default")
      (node (ref "U6") (pin "3") (pinfunction "OUT_3_3") (pintype "output"))
    )
    (net (code "64") (name "unconnected-(U7-IN_2-Pad7)") (class "Default")
      (node (ref "U7") (pin "7") (pinfunction "IN_2_7") (pintype "input"))
    )
    (net (code "65") (name "unconnected-(U7-NC-Pad6)") (class "Default")
      (node (ref "U7") (pin "6") (pinfunction "NC_6") (pintype "no_connect"))
    )
    (net (code "66") (name "unconnected-(U7-NC_2-Pad1)") (class "Default")
      (node (ref "U7") (pin "1") (pinfunction "NC_2_1") (pintype "no_connect"))
    )
    (net (code "67") (name "unconnected-(U7-OUT_2-Pad2)") (class "Default")
      (node (ref "U7") (pin "2") (pinfunction "OUT_2_2") (pintype "output"))
    )
    (net (code "68") (name "unconnected-(U7-OUT_3-Pad3)") (class "Default")
      (node (ref "U7") (pin "3") (pinfunction "OUT_3_3") (pintype "output"))
    )
    (net (code "69") (name "unconnected-(U8-IN_2-Pad7)") (class "Default")
      (node (ref "U8") (pin "7") (pinfunction "IN_2_7") (pintype "input"))
    )
    (net (code "70") (name "unconnected-(U8-NC-Pad6)") (class "Default")
      (node (ref "U8") (pin "6") (pinfunction "NC_6") (pintype "no_connect"))
    )
    (net (code "71") (name "unconnected-(U8-NC_2-Pad1)") (class "Default")
      (node (ref "U8") (pin "1") (pinfunction "NC_2_1") (pintype "no_connect"))
    )
    (net (code "72") (name "unconnected-(U8-OUT_2-Pad2)") (class "Default")
      (node (ref "U8") (pin "2") (pinfunction "OUT_2_2") (pintype "output"))
    )
    (net (code "73") (name "unconnected-(U8-OUT_3-Pad3)") (class "Default")
      (node (ref "U8") (pin "3") (pinfunction "OUT_3_3") (pintype "output"))
    )
  )
)
